# XH-DSP.net
KiCad netlist of a schematic drawn in Altium Designer
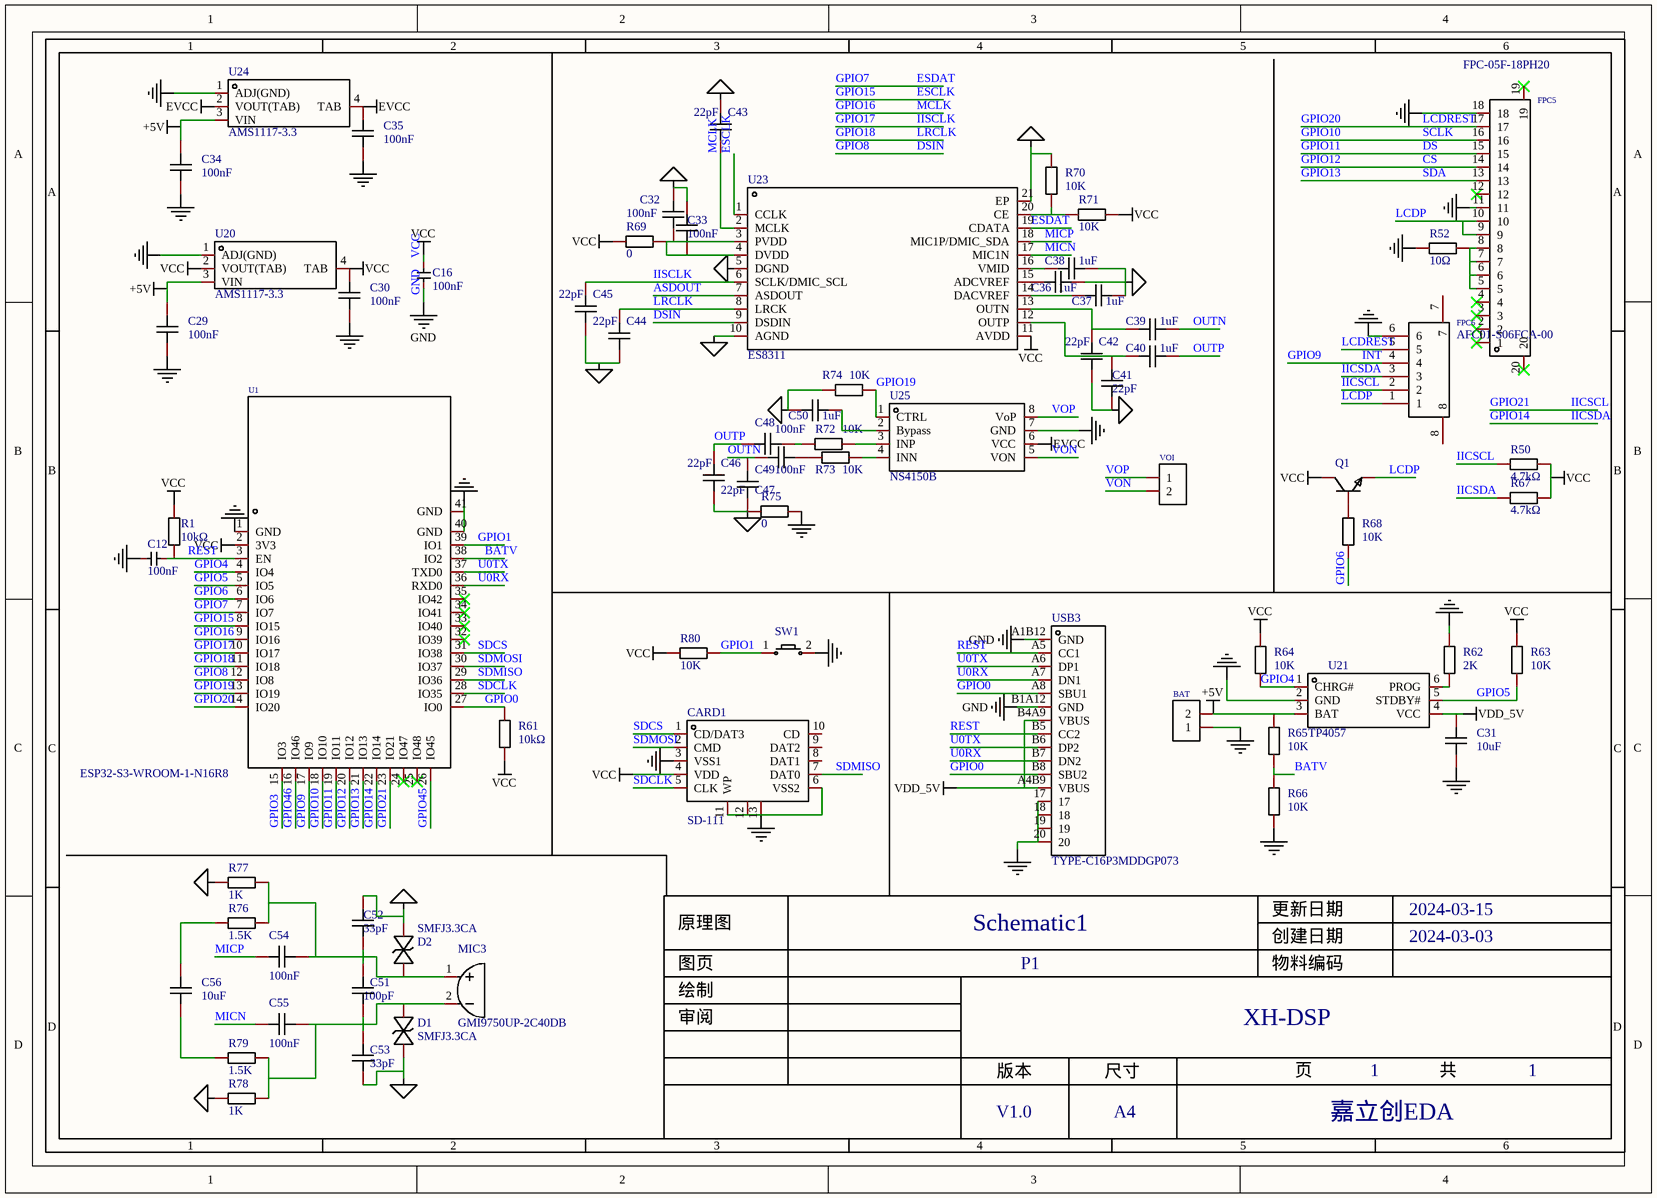
[diagram p0: XH-DSP.schdoc]

(export (version "E")
  (design (tool "Eeschema 10.0.6"))
  (components
    (comp (ref "BAT")
      (value "HDR-F_2.54_1x2P")
      (fields (field (name "MANUFACTURER") "BOOMELE(博穆精密)") (field (name "MANUFACTURER PART") "2.54-1*2P母"))
      (libsource (lib "altium-import") (part "root_2_HDR-F_2.54_1x2P_"))
    )
    (comp (ref "C12")
      (value "100nF")
      (description "容值:100nF;精度:±10%;额定电压:16V;材质(温度系数):X7R;")
      (fields
        (field (name "NAME") "100nF")
        (field (name "MANUFACTURER") "SAMSUNG(三星)")
        (field (name "MANUFACTURER PART") "CL05B104KO5NNNC")
      )
      (libsource (lib "altium-import") (part "root_2_CL05B104KO5NNNC_"))
    )
    (comp (ref "C16")
      (value "100nF")
      (description "容值:100nF;精度:±10%;额定电压:16V;材质(温度系数):X7R;")
      (fields
        (field (name "NAME") "100nF")
        (field (name "MANUFACTURER") "SAMSUNG(三星)")
        (field (name "MANUFACTURER PART") "CL05B104KO5NNNC")
      )
      (libsource (lib "altium-import") (part "root_1_CL05B104KO5NNNC_"))
    )
    (comp (ref "C29")
      (value "100nF")
      (fields
        (field (name "NAME") "100nF")
        (field (name "MANUFACTURER") "FH(风华)")
        (field (name "MANUFACTURER PART") "0805B104K500NT")
        (field (name "TOLERANCE") "±10%")
      )
      (libsource (lib "altium-import") (part "root_1_0805B104K500NT_"))
    )
    (comp (ref "C30")
      (value "100nF")
      (fields
        (field (name "NAME") "100nF")
        (field (name "MANUFACTURER") "FH(风华)")
        (field (name "MANUFACTURER PART") "0805B104K500NT")
        (field (name "TOLERANCE") "±10%")
      )
      (libsource (lib "altium-import") (part "root_1_0805B104K500NT_"))
    )
    (comp (ref "C31")
      (value "10uF")
      (fields (field (name "NAME") "10uF"))
      (libsource (lib "altium-import") (part "root_1_CAP_0603_"))
    )
    (comp (ref "C32")
      (value "100nF")
      (fields (field (name "NAME") "100nF"))
      (libsource (lib "altium-import") (part "root_1_CAP_0402_"))
    )
    (comp (ref "C33")
      (value "100nF")
      (fields (field (name "NAME") "100nF"))
      (libsource (lib "altium-import") (part "root_1_CAP_0402_"))
    )
    (comp (ref "C34")
      (value "100nF")
      (fields
        (field (name "NAME") "100nF")
        (field (name "MANUFACTURER") "FH(风华)")
        (field (name "MANUFACTURER PART") "0805B104K500NT")
        (field (name "TOLERANCE") "±10%")
      )
      (libsource (lib "altium-import") (part "root_1_0805B104K500NT_"))
    )
    (comp (ref "C35")
      (value "100nF")
      (fields
        (field (name "NAME") "100nF")
        (field (name "MANUFACTURER") "FH(风华)")
        (field (name "MANUFACTURER PART") "0805B104K500NT")
        (field (name "TOLERANCE") "±10%")
      )
      (libsource (lib "altium-import") (part "root_1_0805B104K500NT_"))
    )
    (comp (ref "C36")
      (value "1uF")
      (fields (field (name "NAME") "1uF"))
      (libsource (lib "altium-import") (part "root_0_CAP_0402_"))
    )
    (comp (ref "C37")
      (value "1uF")
      (fields (field (name "NAME") "1uF"))
      (libsource (lib "altium-import") (part "root_0_CAP_0402_"))
    )
    (comp (ref "C38")
      (value "1uF")
      (fields (field (name "NAME") "1uF"))
      (libsource (lib "altium-import") (part "root_0_CAP_0402_"))
    )
    (comp (ref "C39")
      (value "1uF")
      (fields (field (name "NAME") "1uF"))
      (libsource (lib "altium-import") (part "root_0_CAP_0402_"))
    )
    (comp (ref "C40")
      (value "1uF")
      (fields (field (name "NAME") "1uF"))
      (libsource (lib "altium-import") (part "root_0_CAP_0402_"))
    )
    (comp (ref "C41")
      (value "22pF")
      (fields (field (name "NAME") "22pF"))
      (libsource (lib "altium-import") (part "root_1_CAP_0402_"))
    )
    (comp (ref "C42")
      (value "22pF")
      (fields (field (name "NAME") "22pF"))
      (libsource (lib "altium-import") (part "root_1_CAP_0402_"))
    )
    (comp (ref "C43")
      (value "22pF")
      (fields (field (name "NAME") "22pF"))
      (libsource (lib "altium-import") (part "root_1_CAP_0402_"))
    )
    (comp (ref "C44")
      (value "22pF")
      (fields (field (name "NAME") "22pF"))
      (libsource (lib "altium-import") (part "root_1_CAP_0402_"))
    )
    (comp (ref "C45")
      (value "22pF")
      (fields (field (name "NAME") "22pF"))
      (libsource (lib "altium-import") (part "root_1_CAP_0402_"))
    )
    (comp (ref "C46")
      (value "22pF")
      (fields (field (name "NAME") "22pF"))
      (libsource (lib "altium-import") (part "root_1_CAP_0402_"))
    )
    (comp (ref "C47")
      (value "22pF")
      (fields (field (name "NAME") "22pF"))
      (libsource (lib "altium-import") (part "root_1_CAP_0402_"))
    )
    (comp (ref "C48")
      (value "100nF")
      (fields (field (name "NAME") "100nF"))
      (libsource (lib "altium-import") (part "root_0_CAP_0402_"))
    )
    (comp (ref "C49")
      (value "100nF")
      (fields (field (name "NAME") "100nF"))
      (libsource (lib "altium-import") (part "root_0_CAP_0402_"))
    )
    (comp (ref "C50")
      (value "1uF")
      (fields (field (name "NAME") "1uF"))
      (libsource (lib "altium-import") (part "root_0_CAP_0402_"))
    )
    (comp (ref "C51")
      (value "100pF")
      (fields (field (name "NAME") "100pF"))
      (libsource (lib "altium-import") (part "root_1_CAP_0402_"))
    )
    (comp (ref "C52")
      (value "33pF")
      (fields (field (name "NAME") "33pF"))
      (libsource (lib "altium-import") (part "root_1_CAP_0402_"))
    )
    (comp (ref "C53")
      (value "33pF")
      (fields (field (name "NAME") "33pF"))
      (libsource (lib "altium-import") (part "root_1_CAP_0402_"))
    )
    (comp (ref "C54")
      (value "100nF")
      (fields (field (name "NAME") "100nF"))
      (libsource (lib "altium-import") (part "root_0_CAP_0402_"))
    )
    (comp (ref "C55")
      (value "100nF")
      (fields (field (name "NAME") "100nF"))
      (libsource (lib "altium-import") (part "root_0_CAP_0402_"))
    )
    (comp (ref "C56")
      (value "10uF")
      (fields (field (name "NAME") "10uF"))
      (libsource (lib "altium-import") (part "root_1_CAP_0402_"))
    )
    (comp (ref "CARD1")
      (value "SD-111")
      (description "卡连接方式:自弹式;卡类型:标准SD卡;连接器类型:卡座;本体最大高度:2.9mm;触头镀层:镀金;工作温度范围:-45℃~+85℃;")
      (fields (field (name "NAME") "SD-111") (field (name "MANUFACTURER") "HANBO(汉博)"))
      (libsource (lib "altium-import") (part "root_0_SD-111_"))
    )
    (comp (ref "D1")
      (value "SMFJ3.3CA")
      (description "SOD-123 200W  VRWM=3.3V 双向 功率TVS 电源口等")
      (fields (field (name "NAME") "SMFJ3.3CA") (field (name "MANUFACTURER") "BORN(伯恩半导体)"))
      (libsource (lib "altium-import") (part "root_1_SMFJ3.3CA_"))
    )
    (comp (ref "D2")
      (value "SMFJ3.3CA")
      (description "SOD-123 200W  VRWM=3.3V 双向 功率TVS 电源口等")
      (fields (field (name "NAME") "SMFJ3.3CA") (field (name "MANUFACTURER") "BORN(伯恩半导体)"))
      (libsource (lib "altium-import") (part "root_1_SMFJ3.3CA_"))
    )
    (comp (ref "FPC5")
      (value "FPC-05F-18PH20")
      (description "间距:0.5mm;触点数量:18P;锁定特性:翻盖式;安装类型:卧贴;触点类型:下接;工作温度范围:-25℃~+85℃;")
      (fields (field (name "NAME") "FPC-05F-18PH20") (field (name "MANUFACTURER") "XUNPU(讯普)"))
      (libsource (lib "altium-import") (part "root_2_mirrored_FPC-05F-18PH20_"))
    )
    (comp (ref "FPC6")
      (value "AFC01-S06FCA-00")
      (description "间距:0.5mm;触点数量:6;锁定特性:翻盖式;安装类型:卧贴;触点类型:下接;")
      (fields (field (name "NAME") "AFC01-S06FCA-00") (field (name "MANUFACTURER") "JS(钜硕电子)"))
      (libsource (lib "altium-import") (part "root_2_mirrored_AFC01-S06FCA-00_"))
    )
    (comp (ref "MIC3")
      (value "GMI9750UP-2C40DB")
      (fields (field (name "NAME") "GMI9750UP-2C40DB") (field (name "MANUFACTURER") "INGHAi(赢海)"))
      (libsource (lib "altium-import") (part "root_3_GMI9750UP-2C40DB_"))
    )
    (comp (ref "Q1") (value "S8050_SOT_NPN") (libsource (lib "altium-import") (part "root_1_S8050_SOT_NPN_")))
    (comp (ref "R1")
      (value "10kΩ")
      (fields
        (field (name "NAME") "10kΩ")
        (field (name "MANUFACTURER") "UNI-ROYAL(厚声)")
        (field (name "MANUFACTURER PART") "0603WAF1002T5E")
        (field (name "TOLERANCE") "±1%")
      )
      (libsource (lib "altium-import") (part "root_1_0603WAF1002T5E_"))
    )
    (comp (ref "R50")
      (value "4.7kΩ")
      (fields
        (field (name "NAME") "4.7kΩ")
        (field (name "MANUFACTURER") "UNI-ROYAL(厚声)")
        (field (name "MANUFACTURER PART") "0402WGF4701TCE")
        (field (name "TOLERANCE") "±1%")
      )
      (libsource (lib "altium-import") (part "root_0_0402WGF4701TCE_"))
    )
    (comp (ref "R52")
      (value "10Ω")
      (fields
        (field (name "NAME") "10Ω")
        (field (name "MANUFACTURER") "UNI-ROYAL(厚声)")
        (field (name "MANUFACTURER PART") "0402WGF100JTCE")
        (field (name "TOLERANCE") "±1%")
      )
      (libsource (lib "altium-import") (part "root_2_0402WGF100JTCE_"))
    )
    (comp (ref "R61")
      (value "10kΩ")
      (fields
        (field (name "NAME") "10kΩ")
        (field (name "MANUFACTURER") "UNI-ROYAL(厚声)")
        (field (name "MANUFACTURER PART") "0603WAF1002T5E")
        (field (name "TOLERANCE") "±1%")
      )
      (libsource (lib "altium-import") (part "root_1_0603WAF1002T5E_"))
    )
    (comp (ref "R62")
      (value "2K")
      (fields (field (name "NAME") "2K"))
      (libsource (lib "altium-import") (part "root_1_Res_0402_"))
    )
    (comp (ref "R63")
      (value "10K")
      (fields (field (name "NAME") "10K"))
      (libsource (lib "altium-import") (part "root_1_Res_0603_"))
    )
    (comp (ref "R64")
      (value "10K")
      (fields (field (name "NAME") "10K"))
      (libsource (lib "altium-import") (part "root_1_Res_0603_"))
    )
    (comp (ref "R65")
      (value "10K")
      (fields (field (name "NAME") "10K"))
      (libsource (lib "altium-import") (part "root_1_Res_0603_"))
    )
    (comp (ref "R66")
      (value "10K")
      (fields (field (name "NAME") "10K"))
      (libsource (lib "altium-import") (part "root_3_Res_0603_"))
    )
    (comp (ref "R67")
      (value "4.7kΩ")
      (fields
        (field (name "NAME") "4.7kΩ")
        (field (name "MANUFACTURER") "UNI-ROYAL(厚声)")
        (field (name "MANUFACTURER PART") "0402WGF4701TCE")
        (field (name "TOLERANCE") "±1%")
      )
      (libsource (lib "altium-import") (part "root_0_0402WGF4701TCE_"))
    )
    (comp (ref "R68")
      (value "10K")
      (fields (field (name "NAME") "10K"))
      (libsource (lib "altium-import") (part "root_1_Res_0603_"))
    )
    (comp (ref "R69")
      (value "0")
      (fields (field (name "NAME") "0"))
      (libsource (lib "altium-import") (part "root_0_Res_0402_"))
    )
    (comp (ref "R70")
      (value "10K")
      (fields (field (name "NAME") "10K"))
      (libsource (lib "altium-import") (part "root_1_Res_0402_"))
    )
    (comp (ref "R71")
      (value "10K")
      (fields (field (name "NAME") "10K"))
      (libsource (lib "altium-import") (part "root_2_Res_0402_"))
    )
    (comp (ref "R72")
      (value "10K")
      (fields (field (name "NAME") "10K"))
      (libsource (lib "altium-import") (part "root_0_Res_0402_"))
    )
    (comp (ref "R73")
      (value "10K")
      (fields (field (name "NAME") "10K"))
      (libsource (lib "altium-import") (part "root_0_Res_0402_"))
    )
    (comp (ref "R74")
      (value "10K")
      (fields (field (name "NAME") "10K"))
      (libsource (lib "altium-import") (part "root_0_Res_0402_"))
    )
    (comp (ref "R75")
      (value "0")
      (fields (field (name "NAME") "0"))
      (libsource (lib "altium-import") (part "root_0_Res_0402_"))
    )
    (comp (ref "R76")
      (value "1.5K")
      (fields (field (name "NAME") "1.5K"))
      (libsource (lib "altium-import") (part "root_2_Res_0402_"))
    )
    (comp (ref "R77")
      (value "1K")
      (fields (field (name "NAME") "1K"))
      (libsource (lib "altium-import") (part "root_2_Res_0402_"))
    )
    (comp (ref "R78")
      (value "1K")
      (fields (field (name "NAME") "1K"))
      (libsource (lib "altium-import") (part "root_2_Res_0402_"))
    )
    (comp (ref "R79")
      (value "1.5K")
      (fields (field (name "NAME") "1.5K"))
      (libsource (lib "altium-import") (part "root_2_Res_0402_"))
    )
    (comp (ref "R80")
      (value "10K")
      (fields (field (name "NAME") "10K"))
      (libsource (lib "altium-import") (part "root_0_Res_0402_"))
    )
    (comp (ref "SW1")
      (value "Key_SMD_3x4x2")
      (libsource (lib "altium-import") (part "root_0_Key_SMD_3x4x2_"))
    )
    (comp (ref "U1")
      (value "ESP32-S3-WROOM-1-N16R8")
      (fields (field (name "NAME") "ESP32-S3-WROOM-1-N16R8") (field (name "MANUFACTURER") "ESPRESSIF(乐鑫)"))
      (libsource (lib "altium-import") (part "root_0_ESP32-S3-WROOM-1-N16R8_"))
    )
    (comp (ref "U20")
      (value "AMS1117-3.3")
      (description "输出类型:固定;输出极性:正;最大输入电压:18V;输出电压:3.3V;输出电流:1A;电源纹波抑制比(PSRR):60dB@(120Hz);")
      (fields (field (name "NAME") "AMS1117-3.3") (field (name "MANUFACTURER") "UMW(广东友台半导体)"))
      (libsource (lib "altium-import") (part "root_0_AMS1117-3.3_C347222_"))
    )
    (comp (ref "U21")
      (value "TP4057")
      (description "电源电压:6.5V;最大充电电流:500mA;电池类型:锂离子/聚合物;电池节数:1;")
      (fields (field (name "NAME") "TP4057") (field (name "MANUFACTURER") "UMW(友台半导体)"))
      (libsource (lib "altium-import") (part "root_0_TP4057_"))
    )
    (comp (ref "U23")
      (value "ES8311")
      (fields (field (name "NAME") "ES8311") (field (name "MANUFACTURER") "Everest-semi(顺芯)"))
      (libsource (lib "altium-import") (part "root_0_ES8311_"))
    )
    (comp (ref "U24")
      (value "AMS1117-3.3")
      (description "输出类型:固定;输出极性:正;最大输入电压:18V;输出电压:3.3V;输出电流:1A;电源纹波抑制比(PSRR):60dB@(120Hz);")
      (fields (field (name "NAME") "AMS1117-3.3") (field (name "MANUFACTURER") "UMW(广东友台半导体)"))
      (libsource (lib "altium-import") (part "root_0_AMS1117-3.3_C347222_"))
    )
    (comp (ref "U25")
      (value "NS4150B")
      (description "功放类型:D类功放;输出功率:3Wx1@4Ω;")
      (fields (field (name "NAME") "NS4150B") (field (name "MANUFACTURER") "Nsiway(纳芯威)"))
      (libsource (lib "altium-import") (part "root_0_NS4150B_C189961_"))
    )
    (comp (ref "USB3")
      (value "TYPE-C16P3MDDGP073")
      (fields (field (name "NAME") "TYPE-C16P3MDDGP073") (field (name "MANUFACTURER") "SHOU HAN(首韩)"))
      (libsource (lib "altium-import") (part "root_0_TYPE-C16P3MDDGP073_"))
    )
    (comp (ref "VOI")
      (value "HDR-F_2.54_1x2P")
      (fields (field (name "MANUFACTURER") "BOOMELE(博穆精密)") (field (name "MANUFACTURER PART") "2.54-1*2P母"))
      (libsource (lib "altium-import") (part "root_0_HDR-F_2.54_1x2P_"))
    )
  )
  (nets
    (net (code "1") (name "+5V") (class "Default")
      (node (ref "BAT") (pin "2") (pinfunction "2_2") (pintype "passive"))
      (node (ref "C29") (pin "2") (pinfunction "2_2") (pintype "passive"))
      (node (ref "C34") (pin "2") (pinfunction "2_2") (pintype "passive"))
      (node (ref "R65") (pin "2") (pinfunction "2_2") (pintype "passive"))
      (node (ref "U20") (pin "3") (pinfunction "VIN_3") (pintype "passive"))
      (node (ref "U21") (pin "3") (pinfunction "BAT_3") (pintype "passive"))
      (node (ref "U24") (pin "3") (pinfunction "VIN_3") (pintype "passive"))
    )
    (net (code "2") (name "/ASDOUT") (class "Default")
      (node (ref "U23") (pin "7") (pinfunction "ASDOUT_7") (pintype "passive"))
    )
    (net (code "3") (name "/BATV") (class "Default")
      (node (ref "R65") (pin "1") (pinfunction "1_1") (pintype "passive"))
      (node (ref "R66") (pin "1") (pinfunction "1_1") (pintype "passive"))
      (node (ref "U1") (pin "38") (pinfunction "IO2_38") (pintype "passive"))
    )
    (net (code "4") (name "/CS") (class "Default")
      (node (ref "FPC5") (pin "14") (pinfunction "14_14") (pintype "passive"))
      (node (ref "U1") (pin "20") (pinfunction "IO12_20") (pintype "passive"))
    )
    (net (code "5") (name "/DS") (class "Default")
      (node (ref "FPC5") (pin "15") (pinfunction "15_15") (pintype "passive"))
      (node (ref "U1") (pin "19") (pinfunction "IO11_19") (pintype "passive"))
    )
    (net (code "6") (name "/DSIN") (class "Default")
      (node (ref "U1") (pin "12") (pinfunction "IO8_12") (pintype "passive"))
      (node (ref "U23") (pin "9") (pinfunction "DSDIN_9") (pintype "passive"))
    )
    (net (code "7") (name "/ESCLK") (class "Default")
      (node (ref "U1") (pin "8") (pinfunction "IO15_8") (pintype "passive"))
      (node (ref "U23") (pin "1") (pinfunction "CCLK_1") (pintype "passive"))
    )
    (net (code "8") (name "/ESDAT") (class "Default")
      (node (ref "U1") (pin "7") (pinfunction "IO7_7") (pintype "passive"))
      (node (ref "U23") (pin "19") (pinfunction "CDATA_19") (pintype "passive"))
    )
    (net (code "9") (name "/GPIO0") (class "Default")
      (node (ref "R61") (pin "2") (pinfunction "2_2") (pintype "passive"))
      (node (ref "U1") (pin "27") (pinfunction "IO0_27") (pintype "passive"))
      (node (ref "USB3") (pin "A8") (pinfunction "SBU1_A8") (pintype "passive"))
      (node (ref "USB3") (pin "B8") (pinfunction "SBU2_B8") (pintype "passive"))
    )
    (net (code "10") (name "/GPIO1") (class "Default")
      (node (ref "R80") (pin "2") (pinfunction "2_2") (pintype "passive"))
      (node (ref "SW1") (pin "1") (pinfunction "1_1") (pintype "passive"))
      (node (ref "U1") (pin "39") (pinfunction "IO1_39") (pintype "passive"))
    )
    (net (code "11") (name "/GPIO3") (class "Default")
      (node (ref "U1") (pin "15") (pinfunction "IO3_15") (pintype "passive"))
    )
    (net (code "12") (name "/GPIO4") (class "Default")
      (node (ref "R64") (pin "1") (pinfunction "1_1") (pintype "passive"))
      (node (ref "U1") (pin "4") (pinfunction "IO4_4") (pintype "passive"))
      (node (ref "U21") (pin "1") (pinfunction "CHRG#_1") (pintype "passive"))
    )
    (net (code "13") (name "/GPIO5") (class "Default")
      (node (ref "R63") (pin "1") (pinfunction "1_1") (pintype "passive"))
      (node (ref "U1") (pin "5") (pinfunction "IO5_5") (pintype "passive"))
      (node (ref "U21") (pin "5") (pinfunction "STDBY#_5") (pintype "passive"))
    )
    (net (code "14") (name "/GPIO6") (class "Default")
      (node (ref "R68") (pin "1") (pinfunction "1_1") (pintype "passive"))
      (node (ref "U1") (pin "6") (pinfunction "IO6_6") (pintype "passive"))
    )
    (net (code "15") (name "/GPIO9") (class "Default")
      (node (ref "FPC6") (pin "4") (pinfunction "4_4") (pintype "passive"))
      (node (ref "U1") (pin "17") (pinfunction "IO9_17") (pintype "passive"))
    )
    (net (code "16") (name "/GPIO10") (class "Default")
      (node (ref "FPC5") (pin "16") (pinfunction "16_16") (pintype "passive"))
      (node (ref "U1") (pin "18") (pinfunction "IO10_18") (pintype "passive"))
    )
    (net (code "17") (name "/GPIO13") (class "Default")
      (node (ref "FPC5") (pin "13") (pinfunction "13_13") (pintype "passive"))
      (node (ref "U1") (pin "21") (pinfunction "IO13_21") (pintype "passive"))
    )
    (net (code "18") (name "/GPIO14") (class "Default")
      (node (ref "FPC6") (pin "3") (pinfunction "3_3") (pintype "passive"))
      (node (ref "R67") (pin "1") (pinfunction "1_1") (pintype "passive"))
      (node (ref "U1") (pin "22") (pinfunction "IO14_22") (pintype "passive"))
    )
    (net (code "19") (name "/GPIO16") (class "Default")
      (node (ref "C43") (pin "1") (pinfunction "1_1") (pintype "passive"))
      (node (ref "U1") (pin "9") (pinfunction "IO16_9") (pintype "passive"))
      (node (ref "U23") (pin "2") (pinfunction "MCLK_2") (pintype "passive"))
    )
    (net (code "20") (name "/GPIO17") (class "Default")
      (node (ref "C45") (pin "2") (pinfunction "2_2") (pintype "passive"))
      (node (ref "U1") (pin "10") (pinfunction "IO17_10") (pintype "passive"))
      (node (ref "U23") (pin "6") (pinfunction "SCLK/DMIC_SCL_6") (pintype "passive"))
    )
    (net (code "21") (name "/GPIO18") (class "Default")
      (node (ref "C44") (pin "2") (pinfunction "2_2") (pintype "passive"))
      (node (ref "U1") (pin "11") (pinfunction "IO18_11") (pintype "passive"))
      (node (ref "U23") (pin "8") (pinfunction "LRCK_8") (pintype "passive"))
    )
    (net (code "22") (name "/GPIO19") (class "Default")
      (node (ref "R74") (pin "2") (pinfunction "2_2") (pintype "passive"))
      (node (ref "U1") (pin "13") (pinfunction "IO19_13") (pintype "passive"))
      (node (ref "U25") (pin "1") (pinfunction "CTRL_1") (pintype "passive"))
    )
    (net (code "23") (name "/GPIO20") (class "Default")
      (node (ref "FPC5") (pin "17") (pinfunction "17_17") (pintype "passive"))
      (node (ref "FPC6") (pin "5") (pinfunction "5_5") (pintype "passive"))
      (node (ref "U1") (pin "14") (pinfunction "IO20_14") (pintype "passive"))
    )
    (net (code "24") (name "/GPIO21") (class "Default")
      (node (ref "FPC6") (pin "2") (pinfunction "2_2") (pintype "passive"))
      (node (ref "R50") (pin "1") (pinfunction "1_1") (pintype "passive"))
      (node (ref "U1") (pin "23") (pinfunction "IO21_23") (pintype "passive"))
    )
    (net (code "25") (name "/GPIO45") (class "Default")
      (node (ref "U1") (pin "26") (pinfunction "IO45_26") (pintype "passive"))
    )
    (net (code "26") (name "/GPIO46") (class "Default")
      (node (ref "U1") (pin "16") (pinfunction "IO46_16") (pintype "passive"))
    )
    (net (code "27") (name "/LCDP") (class "Default")
      (node (ref "FPC5") (pin "10") (pinfunction "10_10") (pintype "passive"))
      (node (ref "FPC5") (pin "9") (pinfunction "9_9") (pintype "passive"))
      (node (ref "FPC6") (pin "1") (pinfunction "1_1") (pintype "passive"))
      (node (ref "Q1") (pin "2") (pinfunction "2_2") (pintype "passive"))
    )
    (net (code "28") (name "/MICN") (class "Default")
      (node (ref "C55") (pin "1") (pinfunction "1_1") (pintype "passive"))
      (node (ref "U23") (pin "17") (pinfunction "MIC1N_17") (pintype "passive"))
    )
    (net (code "29") (name "/MICP") (class "Default")
      (node (ref "C54") (pin "1") (pinfunction "1_1") (pintype "passive"))
      (node (ref "U23") (pin "18") (pinfunction "MIC1P/DMIC_SDA_18") (pintype "passive"))
    )
    (net (code "30") (name "/OUTN") (class "Default")
      (node (ref "C39") (pin "2") (pinfunction "2_2") (pintype "passive"))
      (node (ref "C47") (pin "2") (pinfunction "2_2") (pintype "passive"))
      (node (ref "C49") (pin "1") (pinfunction "1_1") (pintype "passive"))
    )
    (net (code "31") (name "/OUTP") (class "Default")
      (node (ref "C40") (pin "2") (pinfunction "2_2") (pintype "passive"))
      (node (ref "C46") (pin "2") (pinfunction "2_2") (pintype "passive"))
      (node (ref "C48") (pin "1") (pinfunction "1_1") (pintype "passive"))
    )
    (net (code "32") (name "/REST") (class "Default")
      (node (ref "C12") (pin "1") (pinfunction "1_1") (pintype "passive"))
      (node (ref "R1") (pin "1") (pinfunction "1_1") (pintype "passive"))
      (node (ref "U1") (pin "3") (pinfunction "EN_3") (pintype "passive"))
      (node (ref "USB3") (pin "A5") (pinfunction "CC1_A5") (pintype "passive"))
      (node (ref "USB3") (pin "B5") (pinfunction "CC2_B5") (pintype "passive"))
    )
    (net (code "33") (name "/SDCLK") (class "Default")
      (node (ref "CARD1") (pin "5") (pinfunction "CLK_5") (pintype "passive"))
      (node (ref "U1") (pin "28") (pinfunction "IO35_28") (pintype "passive"))
    )
    (net (code "34") (name "/SDCS") (class "Default")
      (node (ref "CARD1") (pin "1") (pinfunction "CD/DAT3_1") (pintype "passive"))
      (node (ref "U1") (pin "31") (pinfunction "IO38_31") (pintype "passive"))
    )
    (net (code "35") (name "/SDMISO") (class "Default")
      (node (ref "CARD1") (pin "7") (pinfunction "DAT0_7") (pintype "passive"))
      (node (ref "U1") (pin "29") (pinfunction "IO36_29") (pintype "passive"))
    )
    (net (code "36") (name "/SDMOSI") (class "Default")
      (node (ref "CARD1") (pin "2") (pinfunction "CMD_2") (pintype "passive"))
      (node (ref "U1") (pin "30") (pinfunction "IO37_30") (pintype "passive"))
    )
    (net (code "37") (name "/U0RX") (class "Default")
      (node (ref "U1") (pin "36") (pinfunction "RXD0_36") (pintype "passive"))
      (node (ref "USB3") (pin "A7") (pinfunction "DN1_A7") (pintype "passive"))
      (node (ref "USB3") (pin "B7") (pinfunction "DN2_B7") (pintype "passive"))
    )
    (net (code "38") (name "/U0TX") (class "Default")
      (node (ref "U1") (pin "37") (pinfunction "TXD0_37") (pintype "passive"))
      (node (ref "USB3") (pin "A6") (pinfunction "DP1_A6") (pintype "passive"))
      (node (ref "USB3") (pin "B6") (pinfunction "DP2_B6") (pintype "passive"))
    )
    (net (code "39") (name "/VON") (class "Default")
      (node (ref "U25") (pin "5") (pinfunction "VON_5") (pintype "passive"))
      (node (ref "VOI") (pin "2") (pinfunction "2_2") (pintype "passive"))
    )
    (net (code "40") (name "/VOP") (class "Default")
      (node (ref "U25") (pin "8") (pinfunction "VoP_8") (pintype "passive"))
      (node (ref "VOI") (pin "1") (pinfunction "1_1") (pintype "passive"))
    )
    (net (code "41") (name "<NO NET>") (class "Default")
      (node (ref "BAT") (pin "1") (pinfunction "1_1") (pintype "passive"))
      (node (ref "C12") (pin "2") (pinfunction "2_2") (pintype "passive"))
      (node (ref "C29") (pin "1") (pinfunction "1_1") (pintype "passive"))
      (node (ref "C30") (pin "1") (pinfunction "1_1") (pintype "passive"))
      (node (ref "C31") (pin "1") (pinfunction "1_1") (pintype "passive"))
      (node (ref "C32") (pin "2") (pinfunction "2_2") (pintype "passive"))
      (node (ref "C33") (pin "2") (pinfunction "2_2") (pintype "passive"))
      (node (ref "C34") (pin "1") (pinfunction "1_1") (pintype "passive"))
      (node (ref "C35") (pin "1") (pinfunction "1_1") (pintype "passive"))
      (node (ref "C36") (pin "2") (pinfunction "2_2") (pintype "passive"))
      (node (ref "C37") (pin "2") (pinfunction "2_2") (pintype "passive"))
      (node (ref "C38") (pin "2") (pinfunction "2_2") (pintype "passive"))
      (node (ref "C41") (pin "1") (pinfunction "1_1") (pintype "passive"))
      (node (ref "C42") (pin "1") (pinfunction "1_1") (pintype "passive"))
      (node (ref "C43") (pin "2") (pinfunction "2_2") (pintype "passive"))
      (node (ref "C44") (pin "1") (pinfunction "1_1") (pintype "passive"))
      (node (ref "C45") (pin "1") (pinfunction "1_1") (pintype "passive"))
      (node (ref "C46") (pin "1") (pinfunction "1_1") (pintype "passive"))
      (node (ref "C47") (pin "1") (pinfunction "1_1") (pintype "passive"))
      (node (ref "C50") (pin "1") (pinfunction "1_1") (pintype "passive"))
      (node (ref "C52") (pin "2") (pinfunction "2_2") (pintype "passive"))
      (node (ref "C53") (pin "1") (pinfunction "1_1") (pintype "passive"))
      (node (ref "CARD1") (pin "11") (pinfunction "WP_11") (pintype "passive"))
      (node (ref "CARD1") (pin "12") (pinfunction "EP_12") (pintype "passive"))
      (node (ref "CARD1") (pin "13") (pinfunction "EP_13") (pintype "passive"))
      (node (ref "CARD1") (pin "3") (pinfunction "VSS1_3") (pintype "passive"))
      (node (ref "CARD1") (pin "6") (pinfunction "VSS2_6") (pintype "passive"))
      (node (ref "D1") (pin "1") (pinfunction "1_1") (pintype "passive"))
      (node (ref "D2") (pin "2") (pinfunction "2_2") (pintype "passive"))
      (node (ref "FPC5") (pin "11") (pinfunction "11_11") (pintype "passive"))
      (node (ref "FPC5") (pin "18") (pinfunction "18_18") (pintype "passive"))
      (node (ref "FPC6") (pin "6") (pinfunction "6_6") (pintype "passive"))
      (node (ref "R52") (pin "2") (pinfunction "2_2") (pintype "passive"))
      (node (ref "R62") (pin "2") (pinfunction "2_2") (pintype "passive"))
      (node (ref "R66") (pin "2") (pinfunction "2_2") (pintype "passive"))
      (node (ref "R70") (pin "2") (pinfunction "2_2") (pintype "passive"))
      (node (ref "R74") (pin "1") (pinfunction "1_1") (pintype "passive"))
      (node (ref "R75") (pin "1") (pinfunction "1_1") (pintype "passive"))
      (node (ref "R75") (pin "2") (pinfunction "2_2") (pintype "passive"))
      (node (ref "R77") (pin "2") (pinfunction "2_2") (pintype "passive"))
      (node (ref "R78") (pin "2") (pinfunction "2_2") (pintype "passive"))
      (node (ref "SW1") (pin "2") (pinfunction "2_2") (pintype "passive"))
      (node (ref "U1") (pin "1") (pinfunction "GND_1") (pintype "passive"))
      (node (ref "U1") (pin "40") (pinfunction "GND_40") (pintype "passive"))
      (node (ref "U1") (pin "41") (pinfunction "GND_41") (pintype "passive"))
      (node (ref "U20") (pin "1") (pinfunction "ADJ(GND)_1") (pintype "passive"))
      (node (ref "U21") (pin "2") (pinfunction "GND_2") (pintype "passive"))
      (node (ref "U23") (pin "10") (pinfunction "AGND_10") (pintype "passive"))
      (node (ref "U23") (pin "21") (pinfunction "EP_21") (pintype "passive"))
      (node (ref "U23") (pin "5") (pinfunction "DGND_5") (pintype "passive"))
      (node (ref "U24") (pin "1") (pinfunction "ADJ(GND)_1") (pintype "passive"))
      (node (ref "U25") (pin "7") (pinfunction "GND_7") (pintype "passive"))
    )
    (net (code "42") (name "EVCC") (class "Default")
      (node (ref "C35") (pin "2") (pinfunction "2_2") (pintype "passive"))
      (node (ref "U24") (pin "2") (pinfunction "VOUT(TAB)_2") (pintype "passive"))
      (node (ref "U24") (pin "4") (pinfunction "TAB_4") (pintype "passive"))
      (node (ref "U25") (pin "6") (pinfunction "VCC_6") (pintype "passive"))
    )
    (net (code "43") (name "GND") (class "Default")
      (node (ref "C16") (pin "1") (pinfunction "1_1") (pintype "passive"))
      (node (ref "USB3") (pin "17") (pinfunction "17_17") (pintype "passive"))
      (node (ref "USB3") (pin "18") (pinfunction "18_18") (pintype "passive"))
      (node (ref "USB3") (pin "19") (pinfunction "19_19") (pintype "passive"))
      (node (ref "USB3") (pin "20") (pinfunction "20_20") (pintype "passive"))
      (node (ref "USB3") (pin "A1B12") (pinfunction "GND_A1B12") (pintype "passive"))
      (node (ref "USB3") (pin "B1A12") (pinfunction "GND_B1A12") (pintype "passive"))
    )
    (net (code "44") (name "Net-(C48-Pad2)") (class "Default")
      (node (ref "C48") (pin "2") (pinfunction "2_2") (pintype "passive"))
      (node (ref "R72") (pin "1") (pinfunction "1_1") (pintype "passive"))
    )
    (net (code "45") (name "Net-(C49-Pad2)") (class "Default")
      (node (ref "C49") (pin "2") (pinfunction "2_2") (pintype "passive"))
      (node (ref "R73") (pin "1") (pinfunction "1_1") (pintype "passive"))
    )
    (net (code "46") (name "Net-(C51-Pad1)") (class "Default")
      (node (ref "C51") (pin "1") (pinfunction "1_1") (pintype "passive"))
      (node (ref "C53") (pin "2") (pinfunction "2_2") (pintype "passive"))
      (node (ref "C55") (pin "2") (pinfunction "2_2") (pintype "passive"))
      (node (ref "D1") (pin "2") (pinfunction "2_2") (pintype "passive"))
      (node (ref "MIC3") (pin "2") (pinfunction "2_2") (pintype "passive"))
      (node (ref "R78") (pin "1") (pinfunction "1_1") (pintype "passive"))
      (node (ref "R79") (pin "1") (pinfunction "1_1") (pintype "passive"))
    )
    (net (code "47") (name "Net-(C51-Pad2)") (class "Default")
      (node (ref "C51") (pin "2") (pinfunction "2_2") (pintype "passive"))
      (node (ref "C52") (pin "1") (pinfunction "1_1") (pintype "passive"))
      (node (ref "C54") (pin "2") (pinfunction "2_2") (pintype "passive"))
      (node (ref "D2") (pin "1") (pinfunction "1_1") (pintype "passive"))
      (node (ref "MIC3") (pin "1") (pinfunction "1_1") (pintype "passive"))
      (node (ref "R76") (pin "1") (pinfunction "1_1") (pintype "passive"))
      (node (ref "R77") (pin "1") (pinfunction "1_1") (pintype "passive"))
    )
    (net (code "48") (name "Net-(C56-Pad1)") (class "Default")
      (node (ref "C56") (pin "1") (pinfunction "1_1") (pintype "passive"))
      (node (ref "R79") (pin "2") (pinfunction "2_2") (pintype "passive"))
    )
    (net (code "49") (name "Net-(C56-Pad2)") (class "Default")
      (node (ref "C56") (pin "2") (pinfunction "2_2") (pintype "passive"))
      (node (ref "R76") (pin "2") (pinfunction "2_2") (pintype "passive"))
    )
    (net (code "50") (name "Net-(FPC5-Pad5)") (class "Default")
      (node (ref "FPC5") (pin "5") (pinfunction "5_5") (pintype "passive"))
      (node (ref "FPC5") (pin "6") (pinfunction "6_6") (pintype "passive"))
      (node (ref "FPC5") (pin "7") (pinfunction "7_7") (pintype "passive"))
      (node (ref "FPC5") (pin "8") (pinfunction "8_8") (pintype "passive"))
      (node (ref "R52") (pin "1") (pinfunction "1_1") (pintype "passive"))
    )
    (net (code "51") (name "Net-(Q1-Pad1)") (class "Default")
      (node (ref "Q1") (pin "1") (pinfunction "1_1") (pintype "passive"))
      (node (ref "R68") (pin "2") (pinfunction "2_2") (pintype "passive"))
    )
    (net (code "52") (name "Net-(U21-PROG)") (class "Default")
      (node (ref "R62") (pin "1") (pinfunction "1_1") (pintype "passive"))
      (node (ref "U21") (pin "6") (pinfunction "PROG_6") (pintype "passive"))
    )
    (net (code "53") (name "Net-(U23-ADCVREF)") (class "Default")
      (node (ref "C36") (pin "1") (pinfunction "1_1") (pintype "passive"))
      (node (ref "U23") (pin "15") (pinfunction "ADCVREF_15") (pintype "passive"))
    )
    (net (code "54") (name "Net-(U23-CE)") (class "Default")
      (node (ref "R70") (pin "1") (pinfunction "1_1") (pintype "passive"))
      (node (ref "R71") (pin "2") (pinfunction "2_2") (pintype "passive"))
      (node (ref "U23") (pin "20") (pinfunction "CE_20") (pintype "passive"))
    )
    (net (code "55") (name "Net-(U23-DACVREF)") (class "Default")
      (node (ref "C37") (pin "1") (pinfunction "1_1") (pintype "passive"))
      (node (ref "U23") (pin "14") (pinfunction "DACVREF_14") (pintype "passive"))
    )
    (net (code "56") (name "Net-(U23-DVDD)") (class "Default")
      (node (ref "C32") (pin "1") (pinfunction "1_1") (pintype "passive"))
      (node (ref "C33") (pin "1") (pinfunction "1_1") (pintype "passive"))
      (node (ref "R69") (pin "2") (pinfunction "2_2") (pintype "passive"))
      (node (ref "U23") (pin "3") (pinfunction "PVDD_3") (pintype "passive"))
      (node (ref "U23") (pin "4") (pinfunction "DVDD_4") (pintype "passive"))
    )
    (net (code "57") (name "Net-(U23-OUTN)") (class "Default")
      (node (ref "C39") (pin "1") (pinfunction "1_1") (pintype "passive"))
      (node (ref "C42") (pin "2") (pinfunction "2_2") (pintype "passive"))
      (node (ref "U23") (pin "13") (pinfunction "OUTN_13") (pintype "passive"))
    )
    (net (code "58") (name "Net-(U23-OUTP)") (class "Default")
      (node (ref "C40") (pin "1") (pinfunction "1_1") (pintype "passive"))
      (node (ref "C41") (pin "2") (pinfunction "2_2") (pintype "passive"))
      (node (ref "U23") (pin "12") (pinfunction "OUTP_12") (pintype "passive"))
    )
    (net (code "59") (name "Net-(U23-VMID)") (class "Default")
      (node (ref "C38") (pin "1") (pinfunction "1_1") (pintype "passive"))
      (node (ref "U23") (pin "16") (pinfunction "VMID_16") (pintype "passive"))
    )
    (net (code "60") (name "Net-(U25-Bypass)") (class "Default")
      (node (ref "C50") (pin "2") (pinfunction "2_2") (pintype "passive"))
      (node (ref "U25") (pin "2") (pinfunction "Bypass_2") (pintype "passive"))
    )
    (net (code "61") (name "Net-(U25-INN)") (class "Default")
      (node (ref "R73") (pin "2") (pinfunction "2_2") (pintype "passive"))
      (node (ref "U25") (pin "4") (pinfunction "INN_4") (pintype "passive"))
    )
    (net (code "62") (name "Net-(U25-INP)") (class "Default")
      (node (ref "R72") (pin "2") (pinfunction "2_2") (pintype "passive"))
      (node (ref "U25") (pin "3") (pinfunction "INP_3") (pintype "passive"))
    )
    (net (code "63") (name "VCC") (class "Default")
      (node (ref "C16") (pin "2") (pinfunction "2_2") (pintype "passive"))
      (node (ref "C30") (pin "2") (pinfunction "2_2") (pintype "passive"))
      (node (ref "CARD1") (pin "4") (pinfunction "VDD_4") (pintype "passive"))
      (node (ref "Q1") (pin "3") (pinfunction "3_3") (pintype "passive"))
      (node (ref "R1") (pin "2") (pinfunction "2_2") (pintype "passive"))
      (node (ref "R50") (pin "2") (pinfunction "2_2") (pintype "passive"))
      (node (ref "R61") (pin "1") (pinfunction "1_1") (pintype "passive"))
      (node (ref "R63") (pin "2") (pinfunction "2_2") (pintype "passive"))
      (node (ref "R64") (pin "2") (pinfunction "2_2") (pintype "passive"))
      (node (ref "R67") (pin "2") (pinfunction "2_2") (pintype "passive"))
      (node (ref "R69") (pin "1") (pinfunction "1_1") (pintype "passive"))
      (node (ref "R71") (pin "1") (pinfunction "1_1") (pintype "passive"))
      (node (ref "R80") (pin "1") (pinfunction "1_1") (pintype "passive"))
      (node (ref "U1") (pin "2") (pinfunction "3V3_2") (pintype "passive"))
      (node (ref "U20") (pin "2") (pinfunction "VOUT(TAB)_2") (pintype "passive"))
      (node (ref "U20") (pin "4") (pinfunction "TAB_4") (pintype "passive"))
      (node (ref "U23") (pin "11") (pinfunction "AVDD_11") (pintype "passive"))
    )
    (net (code "64") (name "VDD_5V") (class "Default")
      (node (ref "C31") (pin "2") (pinfunction "2_2") (pintype "passive"))
      (node (ref "U21") (pin "4") (pinfunction "VCC_4") (pintype "passive"))
      (node (ref "USB3") (pin "A4B9") (pinfunction "VBUS_A4B9") (pintype "passive"))
      (node (ref "USB3") (pin "B4A9") (pinfunction "VBUS_B4A9") (pintype "passive"))
    )
    (net (code "65") (name "unconnected-(CARD1-CD-Pad10)") (class "Default")
      (node (ref "CARD1") (pin "10") (pinfunction "CD_10") (pintype "passive"))
    )
    (net (code "66") (name "unconnected-(CARD1-DAT1-Pad8)") (class "Default")
      (node (ref "CARD1") (pin "8") (pinfunction "DAT1_8") (pintype "passive"))
    )
    (net (code "67") (name "unconnected-(CARD1-DAT2-Pad9)") (class "Default")
      (node (ref "CARD1") (pin "9") (pinfunction "DAT2_9") (pintype "passive"))
    )
    (net (code "68") (name "unconnected-(FPC5-Pad1)") (class "Default")
      (node (ref "FPC5") (pin "1") (pinfunction "1_1") (pintype "passive+no_connect"))
    )
    (net (code "69") (name "unconnected-(FPC5-Pad2)") (class "Default")
      (node (ref "FPC5") (pin "2") (pinfunction "2_2") (pintype "passive+no_connect"))
    )
    (net (code "70") (name "unconnected-(FPC5-Pad3)") (class "Default")
      (node (ref "FPC5") (pin "3") (pinfunction "3_3") (pintype "passive+no_connect"))
    )
    (net (code "71") (name "unconnected-(FPC5-Pad4)") (class "Default")
      (node (ref "FPC5") (pin "4") (pinfunction "4_4") (pintype "passive+no_connect"))
    )
    (net (code "72") (name "unconnected-(FPC5-Pad12)") (class "Default")
      (node (ref "FPC5") (pin "12") (pinfunction "12_12") (pintype "passive+no_connect"))
    )
    (net (code "73") (name "unconnected-(FPC5-Pad19)") (class "Default")
      (node (ref "FPC5") (pin "19") (pinfunction "19_19") (pintype "passive+no_connect"))
    )
    (net (code "74") (name "unconnected-(FPC5-Pad20)") (class "Default")
      (node (ref "FPC5") (pin "20") (pinfunction "20_20") (pintype "passive+no_connect"))
    )
    (net (code "75") (name "unconnected-(FPC6-Pad7)") (class "Default")
      (node (ref "FPC6") (pin "7") (pinfunction "7_7") (pintype "passive"))
    )
    (net (code "76") (name "unconnected-(FPC6-Pad8)") (class "Default")
      (node (ref "FPC6") (pin "8") (pinfunction "8_8") (pintype "passive"))
    )
    (net (code "77") (name "unconnected-(U1-IO39-Pad32)") (class "Default")
      (node (ref "U1") (pin "32") (pinfunction "IO39_32") (pintype "passive+no_connect"))
    )
    (net (code "78") (name "unconnected-(U1-IO40-Pad33)") (class "Default")
      (node (ref "U1") (pin "33") (pinfunction "IO40_33") (pintype "passive+no_connect"))
    )
    (net (code "79") (name "unconnected-(U1-IO41-Pad34)") (class "Default")
      (node (ref "U1") (pin "34") (pinfunction "IO41_34") (pintype "passive+no_connect"))
    )
    (net (code "80") (name "unconnected-(U1-IO42-Pad35)") (class "Default")
      (node (ref "U1") (pin "35") (pinfunction "IO42_35") (pintype "passive+no_connect"))
    )
    (net (code "81") (name "unconnected-(U1-IO47-Pad24)") (class "Default")
      (node (ref "U1") (pin "24") (pinfunction "IO47_24") (pintype "passive+no_connect"))
    )
    (net (code "82") (name "unconnected-(U1-IO48-Pad25)") (class "Default")
      (node (ref "U1") (pin "25") (pinfunction "IO48_25") (pintype "passive+no_connect"))
    )
  )
)
